# Spectron2.net
KiCad netlist of a schematic drawn in EAGLE
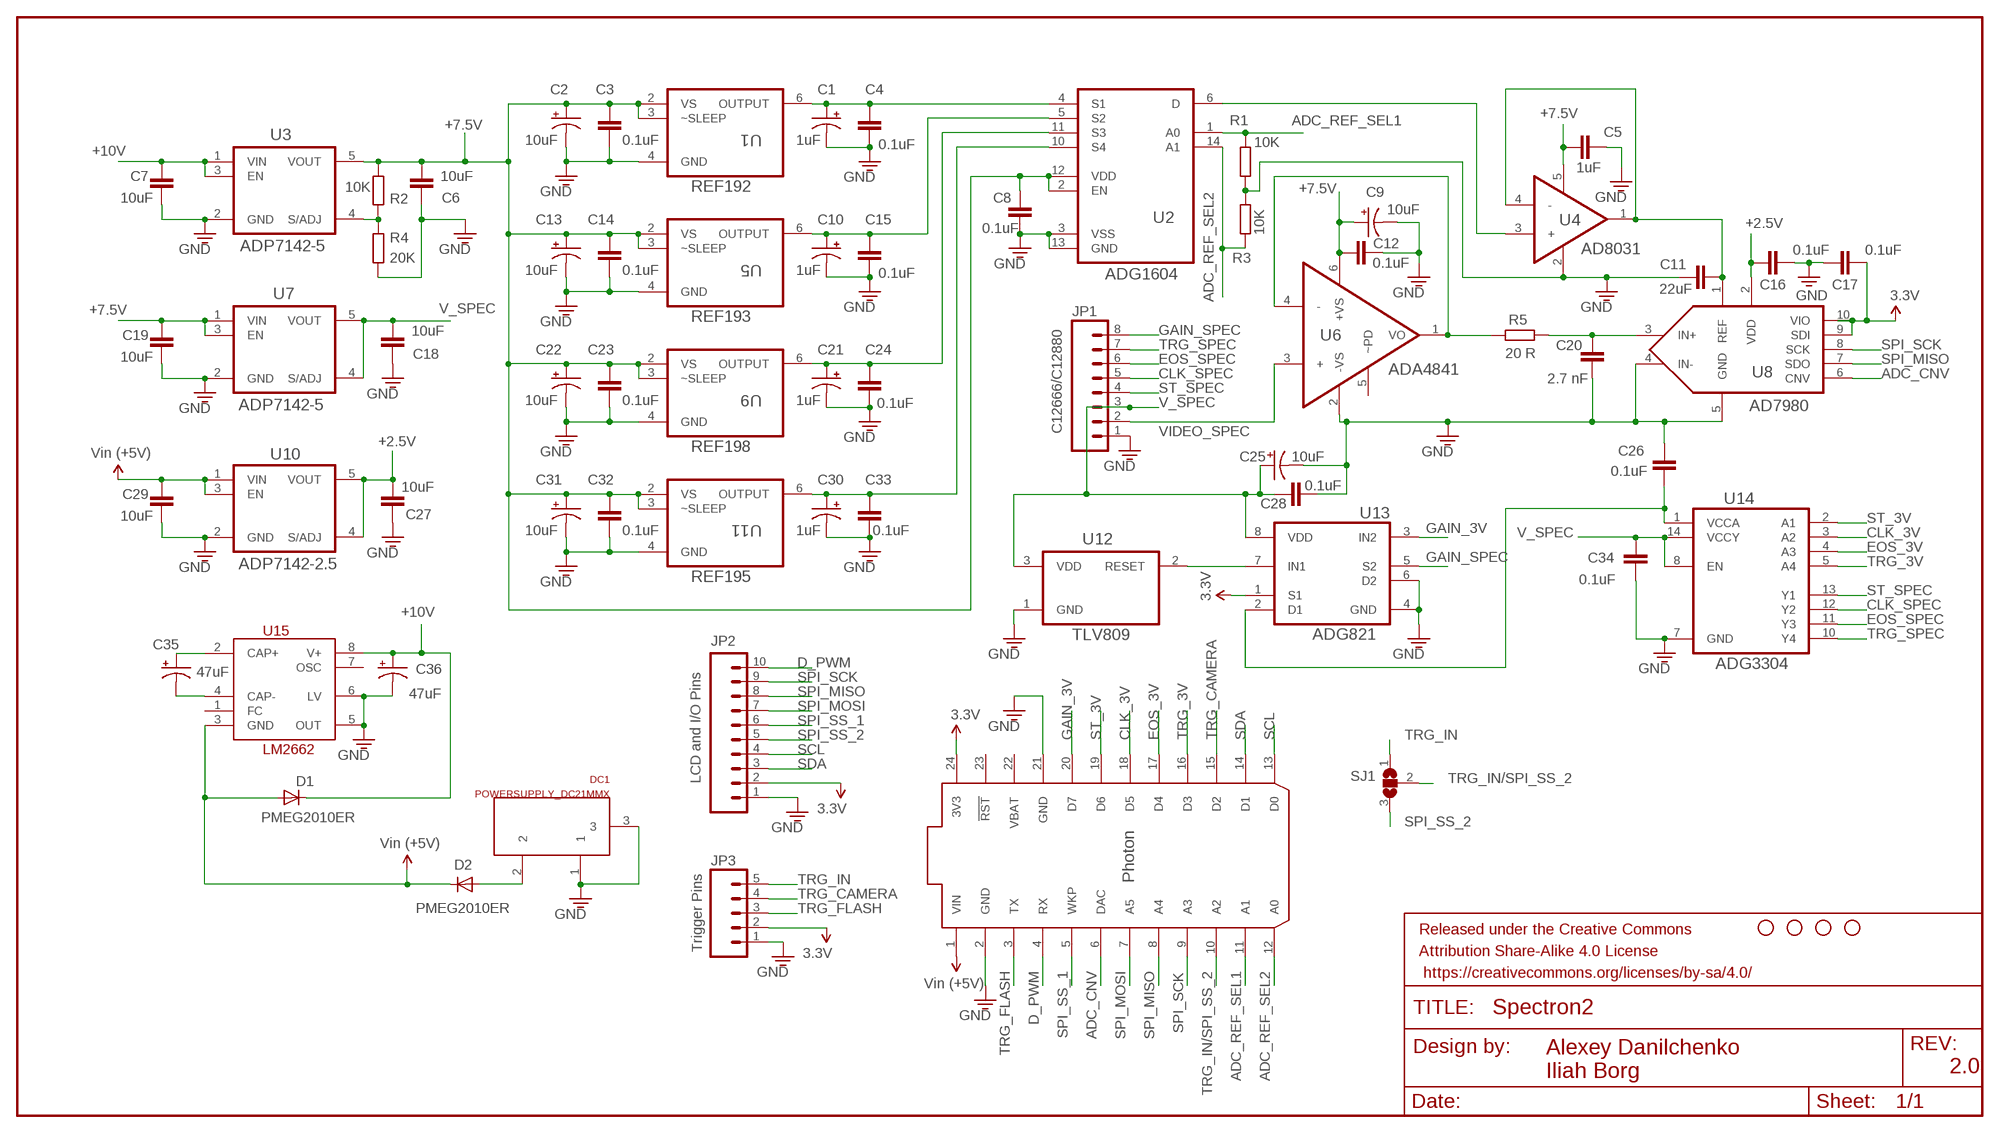
[diagram p0: schematic, sheet 1]

(export (version "E")
  (design (tool "Eeschema 10.0.6"))
  (components
    (comp (ref "C1")
      (value "1uF")
      (footprint "eagle-import:EIA3216")
      (libsource (lib "eagle-import") (part "TANT-CAP1206"))
    )
    (comp (ref "C2")
      (value "10uF")
      (footprint "eagle-import:EIA3216")
      (libsource (lib "eagle-import") (part "Spectron2_TANT-CAP1206"))
    )
    (comp (ref "C3")
      (value "0.1uF")
      (footprint "eagle-import:C0805")
      (libsource (lib "eagle-import") (part "C-EUC0805"))
    )
    (comp (ref "C4")
      (value "0.1uF")
      (footprint "eagle-import:C0805")
      (libsource (lib "eagle-import") (part "C-EUC0805"))
    )
    (comp (ref "C5")
      (value "1uF")
      (footprint "eagle-import:C0805")
      (libsource (lib "eagle-import") (part "C-EUC0805"))
    )
    (comp (ref "C6")
      (value "10uF")
      (footprint "eagle-import:C0805")
      (libsource (lib "eagle-import") (part "C-EUC0805"))
    )
    (comp (ref "C7")
      (value "10uF")
      (footprint "eagle-import:C0805")
      (libsource (lib "eagle-import") (part "C-EUC0805"))
    )
    (comp (ref "C8")
      (value "0.1uF")
      (footprint "eagle-import:C0805")
      (libsource (lib "eagle-import") (part "C-EUC0805"))
    )
    (comp (ref "C9")
      (value "10uF")
      (footprint "eagle-import:EIA3216")
      (libsource (lib "eagle-import") (part "Spectron2_TANT-CAP1206"))
    )
    (comp (ref "C10")
      (value "1uF")
      (footprint "eagle-import:EIA3216")
      (libsource (lib "eagle-import") (part "TANT-CAP1206"))
    )
    (comp (ref "C11")
      (value "22uF")
      (footprint "eagle-import:1206")
      (libsource (lib "eagle-import") (part "CAP1206"))
    )
    (comp (ref "C12")
      (value "0.1uF")
      (footprint "eagle-import:C0805")
      (libsource (lib "eagle-import") (part "C-EUC0805"))
    )
    (comp (ref "C13")
      (value "10uF")
      (footprint "eagle-import:EIA3216")
      (libsource (lib "eagle-import") (part "Spectron2_TANT-CAP1206"))
    )
    (comp (ref "C14")
      (value "0.1uF")
      (footprint "eagle-import:C0805")
      (libsource (lib "eagle-import") (part "C-EUC0805"))
    )
    (comp (ref "C15")
      (value "0.1uF")
      (footprint "eagle-import:C0805")
      (libsource (lib "eagle-import") (part "C-EUC0805"))
    )
    (comp (ref "C16")
      (value "0.1uF")
      (footprint "eagle-import:C0805")
      (libsource (lib "eagle-import") (part "C-EUC0805"))
    )
    (comp (ref "C17")
      (value "0.1uF")
      (footprint "eagle-import:C0805")
      (libsource (lib "eagle-import") (part "C-EUC0805"))
    )
    (comp (ref "C18")
      (value "10uF")
      (footprint "eagle-import:C0805")
      (libsource (lib "eagle-import") (part "C-EUC0805"))
    )
    (comp (ref "C19")
      (value "10uF")
      (footprint "eagle-import:C0805")
      (libsource (lib "eagle-import") (part "C-EUC0805"))
    )
    (comp (ref "C20")
      (value "2.7 nF")
      (footprint "eagle-import:C0805")
      (libsource (lib "eagle-import") (part "C-EUC0805"))
    )
    (comp (ref "C21")
      (value "1uF")
      (footprint "eagle-import:EIA3216")
      (libsource (lib "eagle-import") (part "TANT-CAP1206"))
    )
    (comp (ref "C22")
      (value "10uF")
      (footprint "eagle-import:EIA3216")
      (libsource (lib "eagle-import") (part "Spectron2_TANT-CAP1206"))
    )
    (comp (ref "C23")
      (value "0.1uF")
      (footprint "eagle-import:C0805")
      (libsource (lib "eagle-import") (part "C-EUC0805"))
    )
    (comp (ref "C24")
      (value "0.1uF")
      (footprint "eagle-import:C0805")
      (libsource (lib "eagle-import") (part "C-EUC0805"))
    )
    (comp (ref "C25")
      (value "10uF")
      (footprint "eagle-import:EIA3216")
      (libsource (lib "eagle-import") (part "Spectron2_TANT-CAP1206"))
    )
    (comp (ref "C26")
      (value "0.1uF")
      (footprint "eagle-import:C0805")
      (libsource (lib "eagle-import") (part "C-EUC0805"))
    )
    (comp (ref "C27")
      (value "10uF")
      (footprint "eagle-import:C0805")
      (libsource (lib "eagle-import") (part "C-EUC0805"))
    )
    (comp (ref "C28")
      (value "0.1uF")
      (footprint "eagle-import:C0805")
      (libsource (lib "eagle-import") (part "C-EUC0805"))
    )
    (comp (ref "C29")
      (value "10uF")
      (footprint "eagle-import:C0805")
      (libsource (lib "eagle-import") (part "C-EUC0805"))
    )
    (comp (ref "C30")
      (value "1uF")
      (footprint "eagle-import:EIA3216")
      (libsource (lib "eagle-import") (part "TANT-CAP1206"))
    )
    (comp (ref "C31")
      (value "10uF")
      (footprint "eagle-import:EIA3216")
      (libsource (lib "eagle-import") (part "Spectron2_TANT-CAP1206"))
    )
    (comp (ref "C32")
      (value "0.1uF")
      (footprint "eagle-import:C0805")
      (libsource (lib "eagle-import") (part "C-EUC0805"))
    )
    (comp (ref "C33")
      (value "0.1uF")
      (footprint "eagle-import:C0805")
      (libsource (lib "eagle-import") (part "C-EUC0805"))
    )
    (comp (ref "C34")
      (value "0.1uF")
      (footprint "eagle-import:C0805")
      (libsource (lib "eagle-import") (part "C-EUC0805"))
    )
    (comp (ref "C35")
      (value "47uF")
      (footprint "eagle-import:CT7343")
      (libsource (lib "eagle-import") (part "CPOL-USCT7343"))
    )
    (comp (ref "C36")
      (value "47uF")
      (footprint "eagle-import:CT7343")
      (libsource (lib "eagle-import") (part "CPOL-USCT7343"))
    )
    (comp (ref "D1")
      (value "PMEG2010ER")
      (footprint "eagle-import:SOD123")
      (libsource (lib "eagle-import") (part "DIODE-SOD123"))
    )
    (comp (ref "D2")
      (value "PMEG2010ER")
      (footprint "eagle-import:SOD123")
      (libsource (lib "eagle-import") (part "DIODE-SOD123"))
    )
    (comp (ref "DC1")
      (value "POWERSUPPLY_DC21MMX")
      (footprint "eagle-import:POWERSUPPLY_DC-21MM")
      (libsource (lib "eagle-import") (part "POWERSUPPLY_DC21MMX"))
    )
    (comp (ref "FRAME1")
      (value "FRAME-LEDGER")
      (footprint "eagle-import:CREATIVE_COMMONS")
      (libsource (lib "eagle-import") (part "FRAME-LEDGER"))
    )
    (comp (ref "JP1")
      (value "C12666/C12880")
      (footprint "eagle-import:1X08")
      (libsource (lib "eagle-import") (part "M08SILK_FEMALE_PTH"))
    )
    (comp (ref "JP2")
      (value "LCD and I/O Pins")
      (footprint "eagle-import:1X10")
      (libsource (lib "eagle-import") (part "M10SILK_FEMALE_PTH"))
    )
    (comp (ref "JP3")
      (value "Trigger Pins")
      (footprint "eagle-import:1X05")
      (libsource (lib "eagle-import") (part "M05PTH"))
    )
    (comp (ref "R1")
      (value "10K")
      (footprint "eagle-import:R0805")
      (libsource (lib "eagle-import") (part "R-EU_R0805"))
    )
    (comp (ref "R2")
      (value "10K")
      (footprint "eagle-import:R0805")
      (libsource (lib "eagle-import") (part "R-EU_R0805"))
    )
    (comp (ref "R3")
      (value "10K")
      (footprint "eagle-import:R0805")
      (libsource (lib "eagle-import") (part "R-EU_R0805"))
    )
    (comp (ref "R4")
      (value "20K")
      (footprint "eagle-import:R0805")
      (libsource (lib "eagle-import") (part "R-EU_R0805"))
    )
    (comp (ref "R5")
      (value "20 R")
      (footprint "eagle-import:R0805")
      (libsource (lib "eagle-import") (part "R-EU_R0805"))
    )
    (comp (ref "SJ1")
      (value "SJ2W")
      (footprint "eagle-import:SJ_2")
      (libsource (lib "eagle-import") (part "SJ2W"))
    )
    (comp (ref "STANDOFF1")
      (value "STAND-OFF")
      (footprint "eagle-import:STAND-OFF")
      (libsource (lib "eagle-import") (part "STAND-OFF"))
    )
    (comp (ref "STANDOFF2")
      (value "STAND-OFF")
      (footprint "eagle-import:STAND-OFF")
      (libsource (lib "eagle-import") (part "STAND-OFF"))
    )
    (comp (ref "STANDOFF3")
      (value "STAND-OFF")
      (footprint "eagle-import:STAND-OFF")
      (libsource (lib "eagle-import") (part "STAND-OFF"))
    )
    (comp (ref "STANDOFF4")
      (value "STAND-OFF")
      (footprint "eagle-import:STAND-OFF")
      (libsource (lib "eagle-import") (part "STAND-OFF"))
    )
    (comp (ref "U1")
      (value "REF192")
      (footprint "eagle-import:SOIC127P600X175-8N")
      (libsource (lib "eagle-import") (part "REF192"))
    )
    (comp (ref "U2")
      (value "ADG1604")
      (footprint "eagle-import:SOP65P640X120-14N")
      (fields (field (name "MPN") "ADG1604BRUZ"))
      (libsource (lib "eagle-import") (part "ADG1604"))
    )
    (comp (ref "U3")
      (value "ADP7142-5")
      (footprint "eagle-import:SOT95P280X145-5N")
      (fields (field (name "MPN") "ADP7142"))
      (libsource (lib "eagle-import") (part "ADP7142"))
    )
    (comp (ref "U4")
      (value "AD8031")
      (footprint "eagle-import:SOT95P280X145-5N")
      (libsource (lib "eagle-import") (part "AD8031"))
    )
    (comp (ref "U5")
      (value "REF193")
      (footprint "eagle-import:SOIC127P600X175-8N")
      (libsource (lib "eagle-import") (part "REF193"))
    )
    (comp (ref "U6")
      (value "ADA4841")
      (footprint "eagle-import:SOT95P280X145-6N")
      (fields (field (name "MPN") "ADA4841-1YRJZ-R2"))
      (libsource (lib "eagle-import") (part "ADA4841"))
    )
    (comp (ref "U7")
      (value "ADP7142-5")
      (footprint "eagle-import:SOT95P280X145-5N")
      (fields (field (name "MPN") "ADP7142"))
      (libsource (lib "eagle-import") (part "ADP7142"))
    )
    (comp (ref "U8")
      (value "AD7980")
      (footprint "eagle-import:SOP50P490X110-10N")
      (fields (field (name "MPN") "AD7980ARMZ"))
      (libsource (lib "eagle-import") (part "AD7980"))
    )
    (comp (ref "U9")
      (value "REF198")
      (footprint "eagle-import:SOIC127P600X175-8N")
      (libsource (lib "eagle-import") (part "REF198"))
    )
    (comp (ref "U10")
      (value "ADP7142-2.5")
      (footprint "eagle-import:SOT95P280X145-5N")
      (fields (field (name "MPN") "ADP7142"))
      (libsource (lib "eagle-import") (part "ADP7142"))
    )
    (comp (ref "U11")
      (value "REF195")
      (footprint "eagle-import:SOIC127P600X175-8N")
      (libsource (lib "eagle-import") (part "REF195"))
    )
    (comp (ref "U12")
      (value "TLV809")
      (footprint "eagle-import:SOT95P237X112-3N")
      (fields (field (name "MPN") "TLV80950"))
      (libsource (lib "eagle-import") (part "TLV809"))
    )
    (comp (ref "U13")
      (value "ADG821")
      (footprint "eagle-import:SOP65P490X110-8N")
      (fields (field (name "MPN") "ADG821BRMZ"))
      (libsource (lib "eagle-import") (part "ADG821"))
    )
    (comp (ref "U14")
      (value "ADG3304")
      (footprint "eagle-import:SOP65P640X120-14N")
      (libsource (lib "eagle-import") (part "ADG3304"))
    )
    (comp (ref "U15")
      (value "LM2662")
      (footprint "eagle-import:SOIC8")
      (libsource (lib "eagle-import") (part "LM2662"))
    )
    (comp (ref "U16")
      (value "PHOTON_WITH_HEADERS")
      (footprint "eagle-import:PHOTON")
      (libsource (lib "eagle-import") (part "PHOTON_WITH_HEADERS"))
    )
  )
  (nets
    (net (code "1") (name "/+2.5V") (class "Default")
      (node (ref "C16") (pin "1") (pinfunction "1_1") (pintype "passive"))
      (node (ref "C27") (pin "1") (pinfunction "1_1") (pintype "passive"))
      (node (ref "U10") (pin "4") (pinfunction "S/ADJ_4") (pintype "power_in"))
      (node (ref "U10") (pin "5") (pinfunction "VOUT_5") (pintype "output"))
      (node (ref "U8") (pin "2") (pinfunction "VDD_2") (pintype "power_in"))
    )
    (net (code "2") (name "/+7.5V") (class "Default")
      (node (ref "C12") (pin "2") (pinfunction "2_2") (pintype "passive"))
      (node (ref "C13") (pin "A") (pinfunction "+_A") (pintype "passive"))
      (node (ref "C14") (pin "2") (pinfunction "2_2") (pintype "passive"))
      (node (ref "C19") (pin "2") (pinfunction "2_2") (pintype "passive"))
      (node (ref "C2") (pin "A") (pinfunction "+_A") (pintype "passive"))
      (node (ref "C22") (pin "A") (pinfunction "+_A") (pintype "passive"))
      (node (ref "C23") (pin "2") (pinfunction "2_2") (pintype "passive"))
      (node (ref "C3") (pin "2") (pinfunction "2_2") (pintype "passive"))
      (node (ref "C31") (pin "A") (pinfunction "+_A") (pintype "passive"))
      (node (ref "C32") (pin "2") (pinfunction "2_2") (pintype "passive"))
      (node (ref "C5") (pin "2") (pinfunction "2_2") (pintype "passive"))
      (node (ref "C6") (pin "1") (pinfunction "1_1") (pintype "passive"))
      (node (ref "C8") (pin "2") (pinfunction "2_2") (pintype "passive"))
      (node (ref "C9") (pin "A") (pinfunction "+_A") (pintype "passive"))
      (node (ref "R2") (pin "1") (pinfunction "1_1") (pintype "passive"))
      (node (ref "U1") (pin "2") (pinfunction "VS_2") (pintype "power_in"))
      (node (ref "U1") (pin "3") (pinfunction "~{SLEEP}_3") (pintype "input"))
      (node (ref "U11") (pin "2") (pinfunction "VS_2") (pintype "power_in"))
      (node (ref "U11") (pin "3") (pinfunction "~{SLEEP}_3") (pintype "input"))
      (node (ref "U2") (pin "12") (pinfunction "VDD_12") (pintype "power_in"))
      (node (ref "U2") (pin "2") (pinfunction "EN_2") (pintype "input"))
      (node (ref "U3") (pin "5") (pinfunction "VOUT_5") (pintype "output"))
      (node (ref "U4") (pin "5") (pinfunction "+VS_5") (pintype "power_in"))
      (node (ref "U5") (pin "2") (pinfunction "VS_2") (pintype "power_in"))
      (node (ref "U5") (pin "3") (pinfunction "~{SLEEP}_3") (pintype "input"))
      (node (ref "U6") (pin "6") (pinfunction "+VS_6") (pintype "power_in"))
      (node (ref "U7") (pin "1") (pinfunction "VIN_1") (pintype "input"))
      (node (ref "U7") (pin "3") (pinfunction "EN_3") (pintype "power_in"))
      (node (ref "U9") (pin "2") (pinfunction "VS_2") (pintype "power_in"))
      (node (ref "U9") (pin "3") (pinfunction "~{SLEEP}_3") (pintype "input"))
    )
    (net (code "3") (name "/+10V") (class "Default")
      (node (ref "C36") (pin "+") (pinfunction "+_+") (pintype "passive"))
      (node (ref "C7") (pin "2") (pinfunction "2_2") (pintype "passive"))
      (node (ref "D1") (pin "C") (pinfunction "C_C") (pintype "passive"))
      (node (ref "U15") (pin "8") (pinfunction "V+_8") (pintype "bidirectional"))
      (node (ref "U3") (pin "1") (pinfunction "VIN_1") (pintype "input"))
      (node (ref "U3") (pin "3") (pinfunction "EN_3") (pintype "power_in"))
    )
    (net (code "4") (name "/ADC_CNV") (class "Default")
      (node (ref "U16") (pin "6") (pinfunction "DAC_6") (pintype "bidirectional"))
      (node (ref "U8") (pin "6") (pinfunction "CNV_6") (pintype "input"))
    )
    (net (code "5") (name "/ADC_REF_SEL1") (class "Default")
      (node (ref "R1") (pin "1") (pinfunction "1_1") (pintype "passive"))
      (node (ref "U16") (pin "11") (pinfunction "A1_11") (pintype "bidirectional"))
      (node (ref "U2") (pin "1") (pinfunction "A0_1") (pintype "input"))
    )
    (net (code "6") (name "/ADC_REF_SEL2") (class "Default")
      (node (ref "R3") (pin "2") (pinfunction "2_2") (pintype "passive"))
      (node (ref "U16") (pin "12") (pinfunction "A0_12") (pintype "bidirectional"))
      (node (ref "U2") (pin "14") (pinfunction "A1_14") (pintype "input"))
    )
    (net (code "7") (name "/CLK_3V") (class "Default")
      (node (ref "U14") (pin "3") (pinfunction "A2_3") (pintype "bidirectional"))
      (node (ref "U16") (pin "18") (pinfunction "D5_18") (pintype "bidirectional"))
    )
    (net (code "8") (name "/CLK_SPEC") (class "Default")
      (node (ref "JP1") (pin "5") (pinfunction "5_5") (pintype "passive"))
      (node (ref "U14") (pin "12") (pinfunction "Y2_12") (pintype "bidirectional"))
    )
    (net (code "9") (name "/D_PWM") (class "Default")
      (node (ref "JP2") (pin "10") (pinfunction "10_10") (pintype "passive"))
      (node (ref "U16") (pin "4") (pinfunction "RX_4") (pintype "bidirectional"))
    )
    (net (code "10") (name "/EOS_3V") (class "Default")
      (node (ref "U14") (pin "4") (pinfunction "A3_4") (pintype "bidirectional"))
      (node (ref "U16") (pin "17") (pinfunction "D4_17") (pintype "bidirectional"))
    )
    (net (code "11") (name "/EOS_SPEC") (class "Default")
      (node (ref "JP1") (pin "6") (pinfunction "6_6") (pintype "passive"))
      (node (ref "U14") (pin "11") (pinfunction "Y3_11") (pintype "bidirectional"))
    )
    (net (code "12") (name "/GAIN_3V") (class "Default")
      (node (ref "U13") (pin "3") (pinfunction "IN2_3") (pintype "input"))
      (node (ref "U16") (pin "20") (pinfunction "D7_20") (pintype "bidirectional"))
    )
    (net (code "13") (name "/GAIN_SPEC") (class "Default")
      (node (ref "JP1") (pin "8") (pinfunction "8_8") (pintype "passive"))
      (node (ref "U13") (pin "5") (pinfunction "S2_5") (pintype "bidirectional"))
    )
    (net (code "14") (name "/SCL") (class "Default")
      (node (ref "JP2") (pin "4") (pinfunction "4_4") (pintype "passive"))
      (node (ref "U16") (pin "13") (pinfunction "D0_13") (pintype "bidirectional"))
    )
    (net (code "15") (name "/SDA") (class "Default")
      (node (ref "JP2") (pin "3") (pinfunction "3_3") (pintype "passive"))
      (node (ref "U16") (pin "14") (pinfunction "D1_14") (pintype "bidirectional"))
    )
    (net (code "16") (name "/SPI_MISO") (class "Default")
      (node (ref "JP2") (pin "8") (pinfunction "8_8") (pintype "passive"))
      (node (ref "U16") (pin "8") (pinfunction "A4_8") (pintype "bidirectional"))
      (node (ref "U8") (pin "7") (pinfunction "SDO_7") (pintype "output"))
    )
    (net (code "17") (name "/SPI_MOSI") (class "Default")
      (node (ref "JP2") (pin "7") (pinfunction "7_7") (pintype "passive"))
      (node (ref "U16") (pin "7") (pinfunction "A5_7") (pintype "bidirectional"))
    )
    (net (code "18") (name "/SPI_SCK") (class "Default")
      (node (ref "JP2") (pin "9") (pinfunction "9_9") (pintype "passive"))
      (node (ref "U16") (pin "9") (pinfunction "A3_9") (pintype "bidirectional"))
      (node (ref "U8") (pin "8") (pinfunction "SCK_8") (pintype "input"))
    )
    (net (code "19") (name "/SPI_SS_1") (class "Default")
      (node (ref "JP2") (pin "6") (pinfunction "6_6") (pintype "passive"))
      (node (ref "U16") (pin "5") (pinfunction "WKP_5") (pintype "bidirectional"))
    )
    (net (code "20") (name "/SPI_SS_2") (class "Default")
      (node (ref "JP2") (pin "5") (pinfunction "5_5") (pintype "passive"))
      (node (ref "SJ1") (pin "3") (pinfunction "3_3") (pintype "passive"))
    )
    (net (code "21") (name "/ST_3V") (class "Default")
      (node (ref "U14") (pin "2") (pinfunction "A1_2") (pintype "bidirectional"))
      (node (ref "U16") (pin "19") (pinfunction "D6_19") (pintype "bidirectional"))
    )
    (net (code "22") (name "/ST_SPEC") (class "Default")
      (node (ref "JP1") (pin "4") (pinfunction "4_4") (pintype "passive"))
      (node (ref "U14") (pin "13") (pinfunction "Y1_13") (pintype "bidirectional"))
    )
    (net (code "23") (name "/TRG_3V") (class "Default")
      (node (ref "U14") (pin "5") (pinfunction "A4_5") (pintype "bidirectional"))
      (node (ref "U16") (pin "16") (pinfunction "D3_16") (pintype "bidirectional"))
    )
    (net (code "24") (name "/TRG_CAMERA") (class "Default")
      (node (ref "JP3") (pin "4") (pinfunction "4_4") (pintype "passive"))
      (node (ref "U16") (pin "15") (pinfunction "D2_15") (pintype "bidirectional"))
    )
    (net (code "25") (name "/TRG_FLASH") (class "Default")
      (node (ref "JP3") (pin "3") (pinfunction "3_3") (pintype "passive"))
      (node (ref "U16") (pin "3") (pinfunction "TX_3") (pintype "bidirectional"))
    )
    (net (code "26") (name "/TRG_IN") (class "Default")
      (node (ref "JP3") (pin "5") (pinfunction "5_5") (pintype "passive"))
      (node (ref "SJ1") (pin "1") (pinfunction "1_1") (pintype "passive"))
    )
    (net (code "27") (name "/TRG_IN{slash}SPI_SS_2") (class "Default")
      (node (ref "SJ1") (pin "2") (pinfunction "2_2") (pintype "passive"))
      (node (ref "U16") (pin "10") (pinfunction "A2_10") (pintype "bidirectional"))
    )
    (net (code "28") (name "/TRG_SPEC") (class "Default")
      (node (ref "JP1") (pin "7") (pinfunction "7_7") (pintype "passive"))
      (node (ref "U14") (pin "10") (pinfunction "Y4_10") (pintype "bidirectional"))
    )
    (net (code "29") (name "/VBAT") (class "Default")
      (node (ref "U16") (pin "22") (pinfunction "VBAT_22") (pintype "power_in"))
    )
    (net (code "30") (name "/VIDEO_SPEC") (class "Default")
      (node (ref "JP1") (pin "2") (pinfunction "2_2") (pintype "passive"))
      (node (ref "U6") (pin "3") (pinfunction "+_3") (pintype "input"))
    )
    (net (code "31") (name "/V_SPEC") (class "Default")
      (node (ref "C18") (pin "1") (pinfunction "1_1") (pintype "passive"))
      (node (ref "C25") (pin "A") (pinfunction "+_A") (pintype "passive"))
      (node (ref "C28") (pin "2") (pinfunction "2_2") (pintype "passive"))
      (node (ref "C34") (pin "2") (pinfunction "2_2") (pintype "passive"))
      (node (ref "JP1") (pin "3") (pinfunction "3_3") (pintype "passive"))
      (node (ref "U12") (pin "3") (pinfunction "VDD_3") (pintype "power_in"))
      (node (ref "U13") (pin "8") (pinfunction "VDD_8") (pintype "power_in"))
      (node (ref "U14") (pin "14") (pinfunction "VCCY_14") (pintype "power_in"))
      (node (ref "U14") (pin "8") (pinfunction "EN_8") (pintype "input"))
      (node (ref "U7") (pin "4") (pinfunction "S/ADJ_4") (pintype "power_in"))
      (node (ref "U7") (pin "5") (pinfunction "VOUT_5") (pintype "output"))
    )
    (net (code "32") (name "3.3V") (class "Default")
      (node (ref "C17") (pin "2") (pinfunction "2_2") (pintype "passive"))
      (node (ref "JP2") (pin "2") (pinfunction "2_2") (pintype "passive"))
      (node (ref "JP3") (pin "2") (pinfunction "2_2") (pintype "passive"))
      (node (ref "U13") (pin "1") (pinfunction "S1_1") (pintype "bidirectional"))
      (node (ref "U16") (pin "24") (pinfunction "3V3_24") (pintype "power_in"))
      (node (ref "U8") (pin "10") (pinfunction "VIO_10") (pintype "power_in"))
      (node (ref "U8") (pin "9") (pinfunction "SDI_9") (pintype "input"))
    )
    (net (code "33") (name "GND") (class "Default")
      (node (ref "C1") (pin "C") (pinfunction "-_C") (pintype "passive"))
      (node (ref "C10") (pin "C") (pinfunction "-_C") (pintype "passive"))
      (node (ref "C11") (pin "1") (pinfunction "1_1") (pintype "passive"))
      (node (ref "C12") (pin "1") (pinfunction "1_1") (pintype "passive"))
      (node (ref "C13") (pin "C") (pinfunction "-_C") (pintype "passive"))
      (node (ref "C14") (pin "1") (pinfunction "1_1") (pintype "passive"))
      (node (ref "C15") (pin "1") (pinfunction "1_1") (pintype "passive"))
      (node (ref "C16") (pin "2") (pinfunction "2_2") (pintype "passive"))
      (node (ref "C17") (pin "1") (pinfunction "1_1") (pintype "passive"))
      (node (ref "C18") (pin "2") (pinfunction "2_2") (pintype "passive"))
      (node (ref "C19") (pin "1") (pinfunction "1_1") (pintype "passive"))
      (node (ref "C2") (pin "C") (pinfunction "-_C") (pintype "passive"))
      (node (ref "C20") (pin "1") (pinfunction "1_1") (pintype "passive"))
      (node (ref "C21") (pin "C") (pinfunction "-_C") (pintype "passive"))
      (node (ref "C22") (pin "C") (pinfunction "-_C") (pintype "passive"))
      (node (ref "C23") (pin "1") (pinfunction "1_1") (pintype "passive"))
      (node (ref "C24") (pin "1") (pinfunction "1_1") (pintype "passive"))
      (node (ref "C25") (pin "C") (pinfunction "-_C") (pintype "passive"))
      (node (ref "C26") (pin "2") (pinfunction "2_2") (pintype "passive"))
      (node (ref "C27") (pin "2") (pinfunction "2_2") (pintype "passive"))
      (node (ref "C28") (pin "1") (pinfunction "1_1") (pintype "passive"))
      (node (ref "C29") (pin "1") (pinfunction "1_1") (pintype "passive"))
      (node (ref "C3") (pin "1") (pinfunction "1_1") (pintype "passive"))
      (node (ref "C30") (pin "C") (pinfunction "-_C") (pintype "passive"))
      (node (ref "C31") (pin "C") (pinfunction "-_C") (pintype "passive"))
      (node (ref "C32") (pin "1") (pinfunction "1_1") (pintype "passive"))
      (node (ref "C33") (pin "1") (pinfunction "1_1") (pintype "passive"))
      (node (ref "C34") (pin "1") (pinfunction "1_1") (pintype "passive"))
      (node (ref "C36") (pin "-") (pinfunction "-_-") (pintype "passive"))
      (node (ref "C4") (pin "1") (pinfunction "1_1") (pintype "passive"))
      (node (ref "C5") (pin "1") (pinfunction "1_1") (pintype "passive"))
      (node (ref "C6") (pin "2") (pinfunction "2_2") (pintype "passive"))
      (node (ref "C7") (pin "1") (pinfunction "1_1") (pintype "passive"))
      (node (ref "C8") (pin "1") (pinfunction "1_1") (pintype "passive"))
      (node (ref "C9") (pin "C") (pinfunction "-_C") (pintype "passive"))
      (node (ref "DC1") (pin "1") (pinfunction "1_1") (pintype "power_in"))
      (node (ref "DC1") (pin "3") (pinfunction "3_3") (pintype "power_in"))
      (node (ref "JP1") (pin "1") (pinfunction "1_1") (pintype "passive"))
      (node (ref "JP2") (pin "1") (pinfunction "1_1") (pintype "passive"))
      (node (ref "JP3") (pin "1") (pinfunction "1_1") (pintype "passive"))
      (node (ref "R1") (pin "2") (pinfunction "2_2") (pintype "passive"))
      (node (ref "R3") (pin "1") (pinfunction "1_1") (pintype "passive"))
      (node (ref "R4") (pin "2") (pinfunction "2_2") (pintype "passive"))
      (node (ref "U1") (pin "4") (pinfunction "GND_4") (pintype "passive"))
      (node (ref "U10") (pin "2") (pinfunction "GND_2") (pintype "input"))
      (node (ref "U11") (pin "4") (pinfunction "GND_4") (pintype "passive"))
      (node (ref "U12") (pin "1") (pinfunction "GND_1") (pintype "passive"))
      (node (ref "U13") (pin "4") (pinfunction "GND_4") (pintype "passive"))
      (node (ref "U13") (pin "6") (pinfunction "D2_6") (pintype "bidirectional"))
      (node (ref "U14") (pin "7") (pinfunction "GND_7") (pintype "power_in"))
      (node (ref "U15") (pin "5") (pinfunction "OUT_5") (pintype "bidirectional"))
      (node (ref "U15") (pin "6") (pinfunction "LV_6") (pintype "bidirectional"))
      (node (ref "U16") (pin "2") (pinfunction "GND_2") (pintype "power_in"))
      (node (ref "U16") (pin "21") (pinfunction "GND_21") (pintype "power_in"))
      (node (ref "U2") (pin "13") (pinfunction "GND_13") (pintype "passive"))
      (node (ref "U2") (pin "3") (pinfunction "VSS_3") (pintype "power_in"))
      (node (ref "U3") (pin "2") (pinfunction "GND_2") (pintype "input"))
      (node (ref "U4") (pin "2") (pinfunction "-VS_2") (pintype "power_in"))
      (node (ref "U5") (pin "4") (pinfunction "GND_4") (pintype "passive"))
      (node (ref "U6") (pin "2") (pinfunction "-VS_2") (pintype "power_in"))
      (node (ref "U7") (pin "2") (pinfunction "GND_2") (pintype "input"))
      (node (ref "U8") (pin "4") (pinfunction "IN-_4") (pintype "input"))
      (node (ref "U8") (pin "5") (pinfunction "GND_5") (pintype "passive"))
      (node (ref "U9") (pin "4") (pinfunction "GND_4") (pintype "passive"))
    )
    (net (code "34") (name "Net-(C1-+)") (class "Default")
      (node (ref "C1") (pin "A") (pinfunction "+_A") (pintype "passive"))
      (node (ref "C4") (pin "2") (pinfunction "2_2") (pintype "passive"))
      (node (ref "U1") (pin "6") (pinfunction "OUTPUT_6") (pintype "output"))
      (node (ref "U2") (pin "4") (pinfunction "S1_4") (pintype "bidirectional"))
    )
    (net (code "35") (name "Net-(C10-+)") (class "Default")
      (node (ref "C10") (pin "A") (pinfunction "+_A") (pintype "passive"))
      (node (ref "C15") (pin "2") (pinfunction "2_2") (pintype "passive"))
      (node (ref "U2") (pin "5") (pinfunction "S2_5") (pintype "bidirectional"))
      (node (ref "U5") (pin "6") (pinfunction "OUTPUT_6") (pintype "output"))
    )
    (net (code "36") (name "Net-(C21-+)") (class "Default")
      (node (ref "C21") (pin "A") (pinfunction "+_A") (pintype "passive"))
      (node (ref "C24") (pin "2") (pinfunction "2_2") (pintype "passive"))
      (node (ref "U2") (pin "11") (pinfunction "S3_11") (pintype "bidirectional"))
      (node (ref "U9") (pin "6") (pinfunction "OUTPUT_6") (pintype "output"))
    )
    (net (code "37") (name "Net-(C30-+)") (class "Default")
      (node (ref "C30") (pin "A") (pinfunction "+_A") (pintype "passive"))
      (node (ref "C33") (pin "2") (pinfunction "2_2") (pintype "passive"))
      (node (ref "U11") (pin "6") (pinfunction "OUTPUT_6") (pintype "output"))
      (node (ref "U2") (pin "10") (pinfunction "S4_10") (pintype "bidirectional"))
    )
    (net (code "38") (name "Net-(D2-PadA)") (class "Default")
      (node (ref "D2") (pin "A") (pinfunction "A_A") (pintype "passive"))
      (node (ref "DC1") (pin "2") (pinfunction "2_2") (pintype "power_in"))
    )
    (net (code "39") (name "Net-(U2-D)") (class "Default")
      (node (ref "U2") (pin "6") (pinfunction "D_6") (pintype "bidirectional"))
      (node (ref "U4") (pin "3") (pinfunction "+_3") (pintype "input"))
    )
    (net (code "40") (name "Net-(U3-S{slash}ADJ)") (class "Default")
      (node (ref "R2") (pin "2") (pinfunction "2_2") (pintype "passive"))
      (node (ref "R4") (pin "1") (pinfunction "1_1") (pintype "passive"))
      (node (ref "U3") (pin "4") (pinfunction "S/ADJ_4") (pintype "power_in"))
    )
    (net (code "41") (name "Net-(U4--)") (class "Default")
      (node (ref "C11") (pin "2") (pinfunction "2_2") (pintype "passive"))
      (node (ref "U4") (pin "1") (pinfunction "VOUT_1") (pintype "output"))
      (node (ref "U4") (pin "4") (pinfunction "-_4") (pintype "input"))
      (node (ref "U8") (pin "1") (pinfunction "REF_1") (pintype "input"))
    )
    (net (code "42") (name "Net-(U6--)") (class "Default")
      (node (ref "R5") (pin "2") (pinfunction "2_2") (pintype "passive"))
      (node (ref "U6") (pin "1") (pinfunction "VO_1") (pintype "output"))
      (node (ref "U6") (pin "4") (pinfunction "-_4") (pintype "input"))
    )
    (net (code "43") (name "Net-(U8-IN+)") (class "Default")
      (node (ref "C20") (pin "2") (pinfunction "2_2") (pintype "passive"))
      (node (ref "R5") (pin "1") (pinfunction "1_1") (pintype "passive"))
      (node (ref "U8") (pin "3") (pinfunction "IN+_3") (pintype "input"))
    )
    (net (code "44") (name "Net-(U12-RESET)") (class "Default")
      (node (ref "U12") (pin "2") (pinfunction "RESET_2") (pintype "output"))
      (node (ref "U13") (pin "7") (pinfunction "IN1_7") (pintype "input"))
    )
    (net (code "45") (name "Net-(U13-D1)") (class "Default")
      (node (ref "C26") (pin "1") (pinfunction "1_1") (pintype "passive"))
      (node (ref "U13") (pin "2") (pinfunction "D1_2") (pintype "bidirectional"))
      (node (ref "U14") (pin "1") (pinfunction "VCCA_1") (pintype "power_in"))
    )
    (net (code "46") (name "Net-(U15-CAP+)") (class "Default")
      (node (ref "C35") (pin "+") (pinfunction "+_+") (pintype "passive"))
      (node (ref "U15") (pin "2") (pinfunction "CAP+_2") (pintype "bidirectional"))
    )
    (net (code "47") (name "Net-(U15-CAP-)") (class "Default")
      (node (ref "C35") (pin "-") (pinfunction "-_-") (pintype "passive"))
      (node (ref "U15") (pin "4") (pinfunction "CAP-_4") (pintype "bidirectional"))
    )
    (net (code "48") (name "VIN") (class "Default")
      (node (ref "C29") (pin "2") (pinfunction "2_2") (pintype "passive"))
      (node (ref "D1") (pin "A") (pinfunction "A_A") (pintype "passive"))
      (node (ref "D2") (pin "C") (pinfunction "C_C") (pintype "passive"))
      (node (ref "U10") (pin "1") (pinfunction "VIN_1") (pintype "input"))
      (node (ref "U10") (pin "3") (pinfunction "EN_3") (pintype "power_in"))
      (node (ref "U15") (pin "3") (pinfunction "GND_3") (pintype "bidirectional"))
      (node (ref "U16") (pin "1") (pinfunction "VIN_1") (pintype "power_in"))
    )
    (net (code "49") (name "unconnected-(U6-~{PD}-Pad5)") (class "Default")
      (node (ref "U6") (pin "5") (pinfunction "~{PD}_5") (pintype "input"))
    )
    (net (code "50") (name "unconnected-(U15-FC-Pad1)") (class "Default")
      (node (ref "U15") (pin "1") (pinfunction "FC_1") (pintype "bidirectional"))
    )
    (net (code "51") (name "unconnected-(U15-OSC-Pad7)") (class "Default")
      (node (ref "U15") (pin "7") (pinfunction "OSC_7") (pintype "bidirectional"))
    )
    (net (code "52") (name "unconnected-(U16-~{RST}-Pad23)") (class "Default")
      (node (ref "U16") (pin "23") (pinfunction "~{RST}_23") (pintype "bidirectional"))
    )
  )
)
